# LightingUPS_v2a.net
KiCad netlist of a schematic drawn in EAGLE
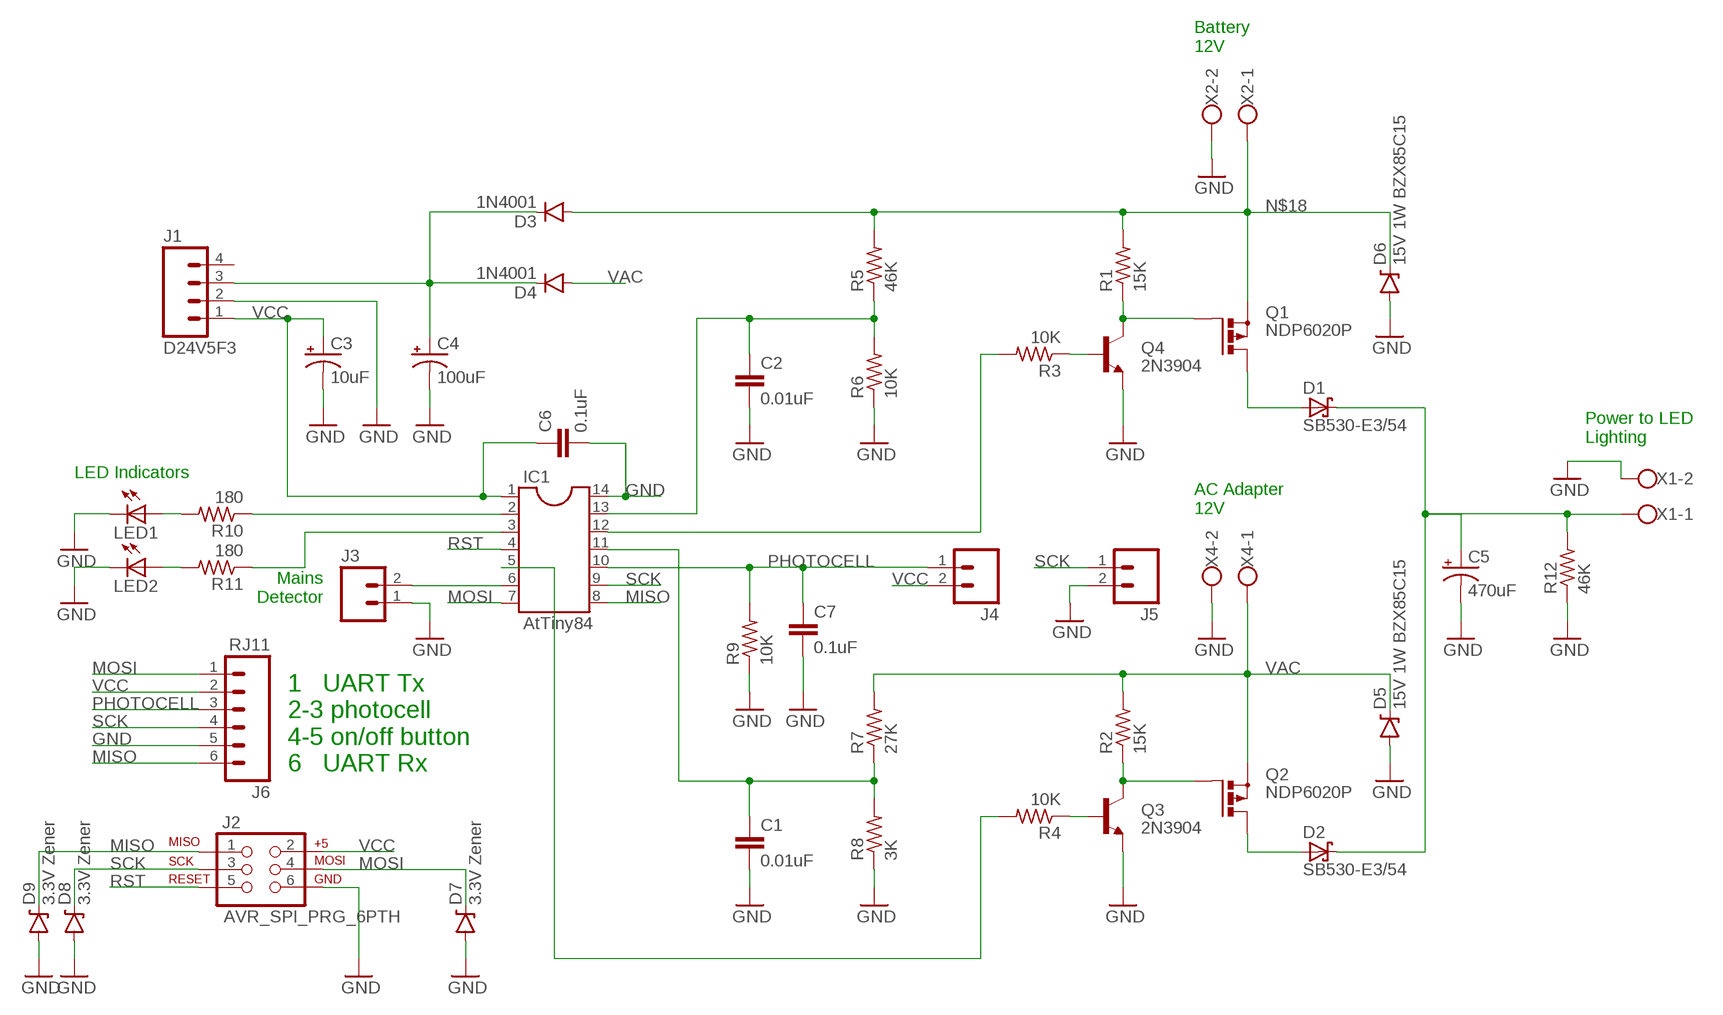
[diagram p0: schematic, sheet 1]

(export (version "E")
  (design (tool "Eeschema 10.0.6"))
  (components
    (comp (ref "C1")
      (value "0.01uF")
      (footprint "eagle-import:CAP-PTH-5MM")
      (libsource (lib "eagle-import") (part "SparkFun-Passives_CAPPTH1"))
    )
    (comp (ref "C2")
      (value "0.01uF")
      (footprint "eagle-import:CAP-PTH-5MM")
      (libsource (lib "eagle-import") (part "SparkFun-Passives_CAPPTH1"))
    )
    (comp (ref "C3")
      (value "10uF")
      (footprint "eagle-import:CPOL-RADIAL-100UF-25V")
      (libsource (lib "eagle-import") (part "CAP_POLPTH1"))
    )
    (comp (ref "C4")
      (value "100uF")
      (footprint "eagle-import:CPOL-RADIAL-100UF-25V")
      (libsource (lib "eagle-import") (part "CAP_POLPTH1"))
    )
    (comp (ref "C5")
      (value "470uF")
      (footprint "eagle-import:CPOL-RADIAL-1000UF-25V")
      (libsource (lib "eagle-import") (part "CAP_POLPTH4"))
    )
    (comp (ref "C6")
      (value "0.1uF")
      (footprint "eagle-import:CAP-PTH-SMALL")
      (libsource (lib "eagle-import") (part "CAPPTH"))
    )
    (comp (ref "C7")
      (value "0.1uF")
      (footprint "eagle-import:CAP-PTH-SMALL")
      (libsource (lib "eagle-import") (part "CAPPTH"))
    )
    (comp (ref "D1")
      (value "SB530-E3/54")
      (footprint "eagle-import:DO201T15")
      (libsource (lib "eagle-import") (part "SCHOTTKY-DIODEDO201T15"))
    )
    (comp (ref "D2")
      (value "SB530-E3/54")
      (footprint "eagle-import:DO201T15")
      (libsource (lib "eagle-import") (part "SCHOTTKY-DIODEDO201T15"))
    )
    (comp (ref "D3")
      (value "1N4001")
      (footprint "eagle-import:DIODE-1N4001")
      (libsource (lib "eagle-import") (part "DIODEPTH"))
    )
    (comp (ref "D4")
      (value "1N4001")
      (footprint "eagle-import:DIODE-1N4001")
      (libsource (lib "eagle-import") (part "DIODEPTH"))
    )
    (comp (ref "D5")
      (value "15V 1W BZX85C15")
      (footprint "eagle-import:DIODE-ZENER")
      (libsource (lib "eagle-import") (part "DIODE-ZENERPTH"))
    )
    (comp (ref "D6")
      (value "15V 1W BZX85C15")
      (footprint "eagle-import:DIODE-ZENER")
      (libsource (lib "eagle-import") (part "DIODE-ZENERPTH"))
    )
    (comp (ref "D7")
      (value "3.3V Zener")
      (footprint "eagle-import:DIODE-ZENER")
      (libsource (lib "eagle-import") (part "DIODE-ZENERPTH"))
    )
    (comp (ref "D8")
      (value "3.3V Zener")
      (footprint "eagle-import:DIODE-ZENER")
      (libsource (lib "eagle-import") (part "DIODE-ZENERPTH"))
    )
    (comp (ref "D9")
      (value "3.3V Zener")
      (footprint "eagle-import:DIODE-ZENER")
      (libsource (lib "eagle-import") (part "DIODE-ZENERPTH"))
    )
    (comp (ref "IC1")
      (value "AtTiny84")
      (footprint "eagle-import:DIL14")
      (libsource (lib "eagle-import") (part "DIL14"))
    )
    (comp (ref "J1")
      (value "D24V5F3")
      (footprint "eagle-import:1X04")
      (libsource (lib "eagle-import") (part "M04PTH"))
    )
    (comp (ref "J2")
      (value "AVR_SPI_PRG_6PTH")
      (footprint "eagle-import:2X3")
      (libsource (lib "eagle-import") (part "AVR_SPI_PRG_6PTH"))
    )
    (comp (ref "J3")
      (value "M02PTH")
      (footprint "eagle-import:1X02")
      (libsource (lib "eagle-import") (part "M02PTH"))
    )
    (comp (ref "J4")
      (value "M02PTH")
      (footprint "eagle-import:1X02")
      (libsource (lib "eagle-import") (part "M02PTH"))
    )
    (comp (ref "J5")
      (value "M02PTH")
      (footprint "eagle-import:1X02")
      (libsource (lib "eagle-import") (part "M02PTH"))
    )
    (comp (ref "J6")
      (value "RJ11")
      (footprint "eagle-import:RJ11-6")
      (libsource (lib "eagle-import") (part "RJ11-6PTH"))
    )
    (comp (ref "LED1")
      (value "LED5MM")
      (footprint "eagle-import:LED5MM")
      (libsource (lib "eagle-import") (part "LED5MM"))
    )
    (comp (ref "LED2")
      (value "LED5MM")
      (footprint "eagle-import:LED5MM")
      (libsource (lib "eagle-import") (part "LED5MM"))
    )
    (comp (ref "Q1")
      (value "NDP6020P")
      (footprint "eagle-import:TO220BV")
      (libsource (lib "eagle-import") (part "PMOSFET_PTO220BV"))
    )
    (comp (ref "Q2")
      (value "NDP6020P")
      (footprint "eagle-import:TO220BV")
      (libsource (lib "eagle-import") (part "PMOSFET_PTO220BV"))
    )
    (comp (ref "Q3")
      (value "2N3904")
      (footprint "eagle-import:TO-92-AMMO")
      (libsource (lib "eagle-import") (part "TRANSISTOR_NPNTO-92-AMMO"))
    )
    (comp (ref "Q4")
      (value "2N3904")
      (footprint "eagle-import:TO-92-AMMO")
      (libsource (lib "eagle-import") (part "TRANSISTOR_NPNTO-92-AMMO"))
    )
    (comp (ref "R1")
      (value "15K")
      (footprint "eagle-import:0204_5")
      (libsource (lib "eagle-import") (part "R-US_0204/5"))
    )
    (comp (ref "R2")
      (value "15K")
      (footprint "eagle-import:0204_5")
      (libsource (lib "eagle-import") (part "R-US_0204/5"))
    )
    (comp (ref "R3")
      (value "10K")
      (footprint "eagle-import:0204_5")
      (libsource (lib "eagle-import") (part "R-US_0204/5"))
    )
    (comp (ref "R4")
      (value "10K")
      (footprint "eagle-import:0204_5")
      (libsource (lib "eagle-import") (part "R-US_0204/5"))
    )
    (comp (ref "R5")
      (value "46K")
      (footprint "eagle-import:0204_5")
      (libsource (lib "eagle-import") (part "R-US_0204/5"))
    )
    (comp (ref "R6")
      (value "10K")
      (footprint "eagle-import:0204_5")
      (libsource (lib "eagle-import") (part "R-US_0204/5"))
    )
    (comp (ref "R7")
      (value "27K")
      (footprint "eagle-import:0204_5")
      (libsource (lib "eagle-import") (part "R-US_0204/5"))
    )
    (comp (ref "R8")
      (value "3K")
      (footprint "eagle-import:0204_5")
      (libsource (lib "eagle-import") (part "R-US_0204/5"))
    )
    (comp (ref "R9")
      (value "10K")
      (footprint "eagle-import:0204_5")
      (libsource (lib "eagle-import") (part "R-US_0204/5"))
    )
    (comp (ref "R10")
      (value "180")
      (footprint "eagle-import:0204_5")
      (libsource (lib "eagle-import") (part "R-US_0204/5"))
    )
    (comp (ref "R11")
      (value "180")
      (footprint "eagle-import:0204_5")
      (libsource (lib "eagle-import") (part "R-US_0204/5"))
    )
    (comp (ref "R12")
      (value "46K")
      (footprint "eagle-import:0204_5")
      (libsource (lib "eagle-import") (part "R-US_0204/5"))
    )
    (comp (ref "X1")
      (value "W237-102")
      (footprint "eagle-import:W237-102")
      (fields (field (name "MPN") "237-102"))
      (libsource (lib "eagle-import") (part "W237-102"))
    )
    (comp (ref "X2")
      (value "W237-102")
      (footprint "eagle-import:W237-102")
      (fields (field (name "MPN") "237-102"))
      (libsource (lib "eagle-import") (part "W237-102"))
    )
    (comp (ref "X4")
      (value "W237-102")
      (footprint "eagle-import:W237-102")
      (fields (field (name "MPN") "237-102"))
      (libsource (lib "eagle-import") (part "W237-102"))
    )
  )
  (nets
    (net (code "1") (name "/MISO") (class "Default")
      (node (ref "D9") (pin "P$1") (pinfunction "C_P$1") (pintype "passive"))
      (node (ref "IC1") (pin "8") (pinfunction "8_8") (pintype "passive"))
      (node (ref "J2") (pin "1") (pinfunction "1_1") (pintype "passive"))
      (node (ref "J6") (pin "6") (pinfunction "6_6") (pintype "passive"))
    )
    (net (code "2") (name "/MOSI") (class "Default")
      (node (ref "D7") (pin "P$1") (pinfunction "C_P$1") (pintype "passive"))
      (node (ref "IC1") (pin "7") (pinfunction "7_7") (pintype "passive"))
      (node (ref "J2") (pin "4") (pinfunction "4_4") (pintype "passive"))
      (node (ref "J6") (pin "1") (pinfunction "1_1") (pintype "passive"))
    )
    (net (code "3") (name "/N$18") (class "Default")
      (node (ref "D3") (pin "A") (pinfunction "A_A") (pintype "passive"))
      (node (ref "D6") (pin "P$1") (pinfunction "C_P$1") (pintype "passive"))
      (node (ref "Q1") (pin "S") (pinfunction "S_S") (pintype "passive"))
      (node (ref "R1") (pin "2") (pinfunction "2_2") (pintype "passive"))
      (node (ref "R5") (pin "2") (pinfunction "2_2") (pintype "passive"))
      (node (ref "X2") (pin "1") (pinfunction "KL_1") (pintype "passive"))
    )
    (net (code "4") (name "/PHOTOCELL") (class "Default")
      (node (ref "C7") (pin "1") (pinfunction "1_1") (pintype "passive"))
      (node (ref "IC1") (pin "10") (pinfunction "10_10") (pintype "passive"))
      (node (ref "J4") (pin "1") (pinfunction "1_1") (pintype "passive"))
      (node (ref "J6") (pin "3") (pinfunction "3_3") (pintype "passive"))
      (node (ref "R9") (pin "2") (pinfunction "2_2") (pintype "passive"))
    )
    (net (code "5") (name "/RST") (class "Default")
      (node (ref "IC1") (pin "4") (pinfunction "4_4") (pintype "passive"))
      (node (ref "J2") (pin "5") (pinfunction "5_5") (pintype "passive"))
    )
    (net (code "6") (name "/SCK") (class "Default")
      (node (ref "D8") (pin "P$1") (pinfunction "C_P$1") (pintype "passive"))
      (node (ref "IC1") (pin "9") (pinfunction "9_9") (pintype "passive"))
      (node (ref "J2") (pin "3") (pinfunction "3_3") (pintype "passive"))
      (node (ref "J5") (pin "1") (pinfunction "1_1") (pintype "passive"))
      (node (ref "J6") (pin "4") (pinfunction "4_4") (pintype "passive"))
    )
    (net (code "7") (name "/VAC") (class "Default")
      (node (ref "D4") (pin "A") (pinfunction "A_A") (pintype "passive"))
      (node (ref "D5") (pin "P$1") (pinfunction "C_P$1") (pintype "passive"))
      (node (ref "Q2") (pin "S") (pinfunction "S_S") (pintype "passive"))
      (node (ref "R2") (pin "2") (pinfunction "2_2") (pintype "passive"))
      (node (ref "R7") (pin "2") (pinfunction "2_2") (pintype "passive"))
      (node (ref "X4") (pin "1") (pinfunction "KL_1") (pintype "passive"))
    )
    (net (code "8") (name "/VCC") (class "Default")
      (node (ref "C3") (pin "1") (pinfunction "+_1") (pintype "passive"))
      (node (ref "C6") (pin "1") (pinfunction "1_1") (pintype "passive"))
      (node (ref "IC1") (pin "1") (pinfunction "1_1") (pintype "passive"))
      (node (ref "J1") (pin "1") (pinfunction "1_1") (pintype "passive"))
      (node (ref "J2") (pin "2") (pinfunction "2_2") (pintype "passive"))
      (node (ref "J4") (pin "2") (pinfunction "2_2") (pintype "passive"))
      (node (ref "J6") (pin "2") (pinfunction "2_2") (pintype "passive"))
    )
    (net (code "9") (name "GND") (class "Default")
      (node (ref "C1") (pin "2") (pinfunction "2_2") (pintype "passive"))
      (node (ref "C2") (pin "2") (pinfunction "2_2") (pintype "passive"))
      (node (ref "C3") (pin "2") (pinfunction "-_2") (pintype "passive"))
      (node (ref "C4") (pin "2") (pinfunction "-_2") (pintype "passive"))
      (node (ref "C5") (pin "-") (pinfunction "-_-") (pintype "passive"))
      (node (ref "C6") (pin "2") (pinfunction "2_2") (pintype "passive"))
      (node (ref "C7") (pin "2") (pinfunction "2_2") (pintype "passive"))
      (node (ref "D5") (pin "P$2") (pinfunction "A_P$2") (pintype "passive"))
      (node (ref "D6") (pin "P$2") (pinfunction "A_P$2") (pintype "passive"))
      (node (ref "D7") (pin "P$2") (pinfunction "A_P$2") (pintype "passive"))
      (node (ref "D8") (pin "P$2") (pinfunction "A_P$2") (pintype "passive"))
      (node (ref "D9") (pin "P$2") (pinfunction "A_P$2") (pintype "passive"))
      (node (ref "IC1") (pin "14") (pinfunction "14_14") (pintype "passive"))
      (node (ref "J1") (pin "2") (pinfunction "2_2") (pintype "passive"))
      (node (ref "J2") (pin "6") (pinfunction "6_6") (pintype "passive"))
      (node (ref "J3") (pin "1") (pinfunction "1_1") (pintype "passive"))
      (node (ref "J5") (pin "2") (pinfunction "2_2") (pintype "passive"))
      (node (ref "J6") (pin "5") (pinfunction "5_5") (pintype "passive"))
      (node (ref "LED1") (pin "K") (pinfunction "C_K") (pintype "passive"))
      (node (ref "LED2") (pin "K") (pinfunction "C_K") (pintype "passive"))
      (node (ref "Q3") (pin "1") (pinfunction "E_1") (pintype "passive"))
      (node (ref "Q4") (pin "1") (pinfunction "E_1") (pintype "passive"))
      (node (ref "R12") (pin "1") (pinfunction "1_1") (pintype "passive"))
      (node (ref "R6") (pin "1") (pinfunction "1_1") (pintype "passive"))
      (node (ref "R8") (pin "1") (pinfunction "1_1") (pintype "passive"))
      (node (ref "R9") (pin "1") (pinfunction "1_1") (pintype "passive"))
      (node (ref "X1") (pin "2") (pinfunction "KL_2") (pintype "passive"))
      (node (ref "X2") (pin "2") (pinfunction "KL_2") (pintype "passive"))
      (node (ref "X4") (pin "2") (pinfunction "KL_2") (pintype "passive"))
    )
    (net (code "10") (name "Net-(C1-Pad1)") (class "Default")
      (node (ref "C1") (pin "1") (pinfunction "1_1") (pintype "passive"))
      (node (ref "IC1") (pin "11") (pinfunction "11_11") (pintype "passive"))
      (node (ref "R7") (pin "1") (pinfunction "1_1") (pintype "passive"))
      (node (ref "R8") (pin "2") (pinfunction "2_2") (pintype "passive"))
    )
    (net (code "11") (name "Net-(C2-Pad1)") (class "Default")
      (node (ref "C2") (pin "1") (pinfunction "1_1") (pintype "passive"))
      (node (ref "IC1") (pin "13") (pinfunction "13_13") (pintype "passive"))
      (node (ref "R5") (pin "1") (pinfunction "1_1") (pintype "passive"))
      (node (ref "R6") (pin "2") (pinfunction "2_2") (pintype "passive"))
    )
    (net (code "12") (name "Net-(C4-+)") (class "Default")
      (node (ref "C4") (pin "1") (pinfunction "+_1") (pintype "passive"))
      (node (ref "D3") (pin "C") (pinfunction "C_C") (pintype "passive"))
      (node (ref "D4") (pin "C") (pinfunction "C_C") (pintype "passive"))
      (node (ref "J1") (pin "3") (pinfunction "3_3") (pintype "passive"))
    )
    (net (code "13") (name "Net-(D1-PadA)") (class "Default")
      (node (ref "D1") (pin "A") (pinfunction "A_A") (pintype "passive"))
      (node (ref "Q1") (pin "D") (pinfunction "D_D") (pintype "passive"))
    )
    (net (code "14") (name "Net-(D2-PadA)") (class "Default")
      (node (ref "D2") (pin "A") (pinfunction "A_A") (pintype "passive"))
      (node (ref "Q2") (pin "D") (pinfunction "D_D") (pintype "passive"))
    )
    (net (code "15") (name "Net-(IC1-Pad2)") (class "Default")
      (node (ref "IC1") (pin "2") (pinfunction "2_2") (pintype "passive"))
      (node (ref "R10") (pin "1") (pinfunction "1_1") (pintype "passive"))
    )
    (net (code "16") (name "Net-(IC1-Pad3)") (class "Default")
      (node (ref "IC1") (pin "3") (pinfunction "3_3") (pintype "passive"))
      (node (ref "R11") (pin "1") (pinfunction "1_1") (pintype "passive"))
    )
    (net (code "17") (name "Net-(IC1-Pad5)") (class "Default")
      (node (ref "IC1") (pin "5") (pinfunction "5_5") (pintype "passive"))
      (node (ref "R4") (pin "2") (pinfunction "2_2") (pintype "passive"))
    )
    (net (code "18") (name "Net-(IC1-Pad6)") (class "Default")
      (node (ref "IC1") (pin "6") (pinfunction "6_6") (pintype "passive"))
      (node (ref "J3") (pin "2") (pinfunction "2_2") (pintype "passive"))
    )
    (net (code "19") (name "Net-(IC1-Pad12)") (class "Default")
      (node (ref "IC1") (pin "12") (pinfunction "12_12") (pintype "passive"))
      (node (ref "R3") (pin "2") (pinfunction "2_2") (pintype "passive"))
    )
    (net (code "20") (name "Net-(LED1-PadA)") (class "Default")
      (node (ref "LED1") (pin "A") (pinfunction "A_A") (pintype "passive"))
      (node (ref "R10") (pin "2") (pinfunction "2_2") (pintype "passive"))
    )
    (net (code "21") (name "Net-(LED2-PadA)") (class "Default")
      (node (ref "LED2") (pin "A") (pinfunction "A_A") (pintype "passive"))
      (node (ref "R11") (pin "2") (pinfunction "2_2") (pintype "passive"))
    )
    (net (code "22") (name "Net-(Q3-B)") (class "Default")
      (node (ref "Q3") (pin "2") (pinfunction "B_2") (pintype "passive"))
      (node (ref "R4") (pin "1") (pinfunction "1_1") (pintype "passive"))
    )
    (net (code "23") (name "Net-(Q3-C)") (class "Default")
      (node (ref "Q2") (pin "G") (pinfunction "G_G") (pintype "passive"))
      (node (ref "Q3") (pin "3") (pinfunction "C_3") (pintype "passive"))
      (node (ref "R2") (pin "1") (pinfunction "1_1") (pintype "passive"))
    )
    (net (code "24") (name "Net-(Q4-B)") (class "Default")
      (node (ref "Q4") (pin "2") (pinfunction "B_2") (pintype "passive"))
      (node (ref "R3") (pin "1") (pinfunction "1_1") (pintype "passive"))
    )
    (net (code "25") (name "Net-(Q4-C)") (class "Default")
      (node (ref "Q1") (pin "G") (pinfunction "G_G") (pintype "passive"))
      (node (ref "Q4") (pin "3") (pinfunction "C_3") (pintype "passive"))
      (node (ref "R1") (pin "1") (pinfunction "1_1") (pintype "passive"))
    )
    (net (code "26") (name "Net-(X1A-KL)") (class "Default")
      (node (ref "C5") (pin "+") (pinfunction "+_+") (pintype "passive"))
      (node (ref "D1") (pin "C") (pinfunction "C_C") (pintype "passive"))
      (node (ref "D2") (pin "C") (pinfunction "C_C") (pintype "passive"))
      (node (ref "R12") (pin "2") (pinfunction "2_2") (pintype "passive"))
      (node (ref "X1") (pin "1") (pinfunction "KL_1") (pintype "passive"))
    )
    (net (code "27") (name "unconnected-(J1-Pad4)") (class "Default")
      (node (ref "J1") (pin "4") (pinfunction "4_4") (pintype "passive"))
    )
  )
)
